# Callisto_MSO_Teknic_4BPico.net
KiCad netlist of a schematic drawn in EAGLE
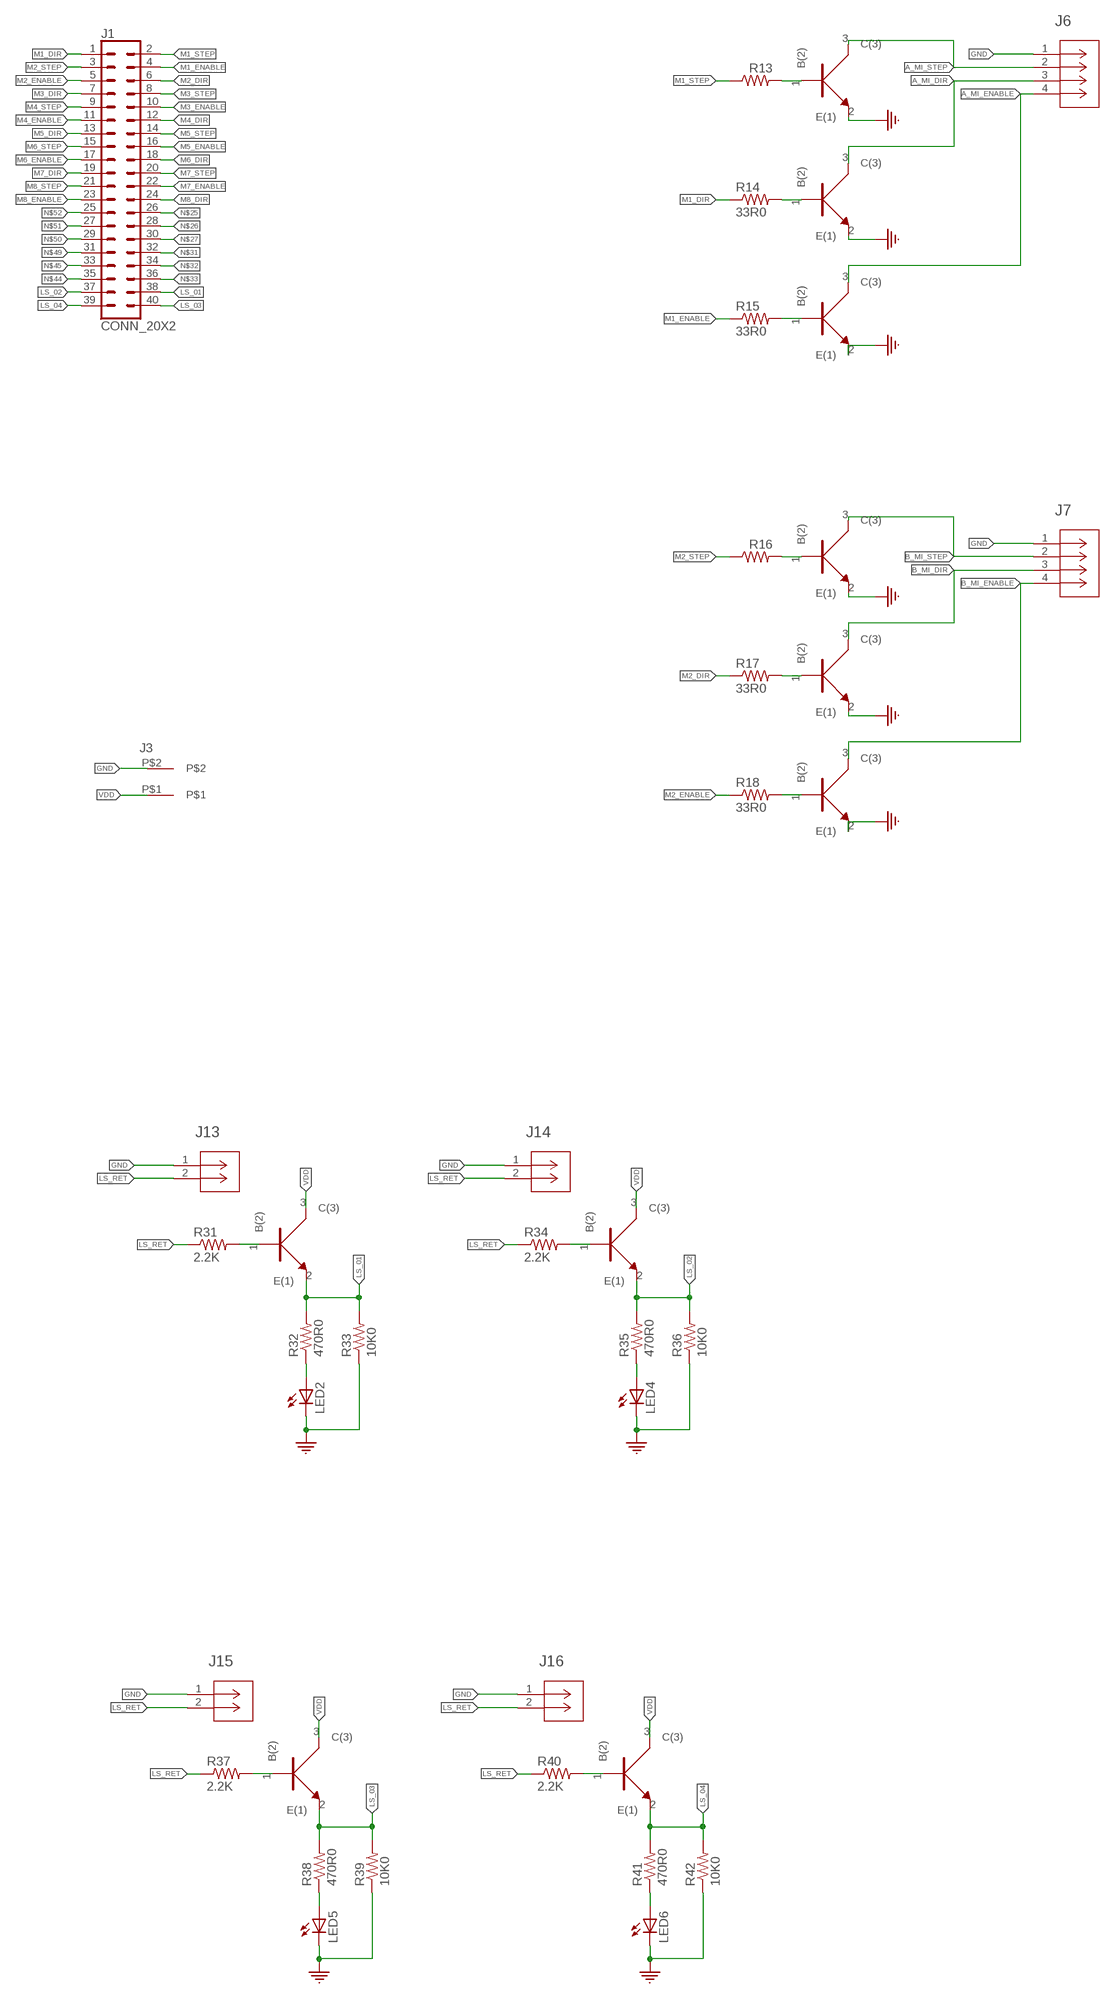
[diagram p0: schematic, sheet 1, part 1 of 2]
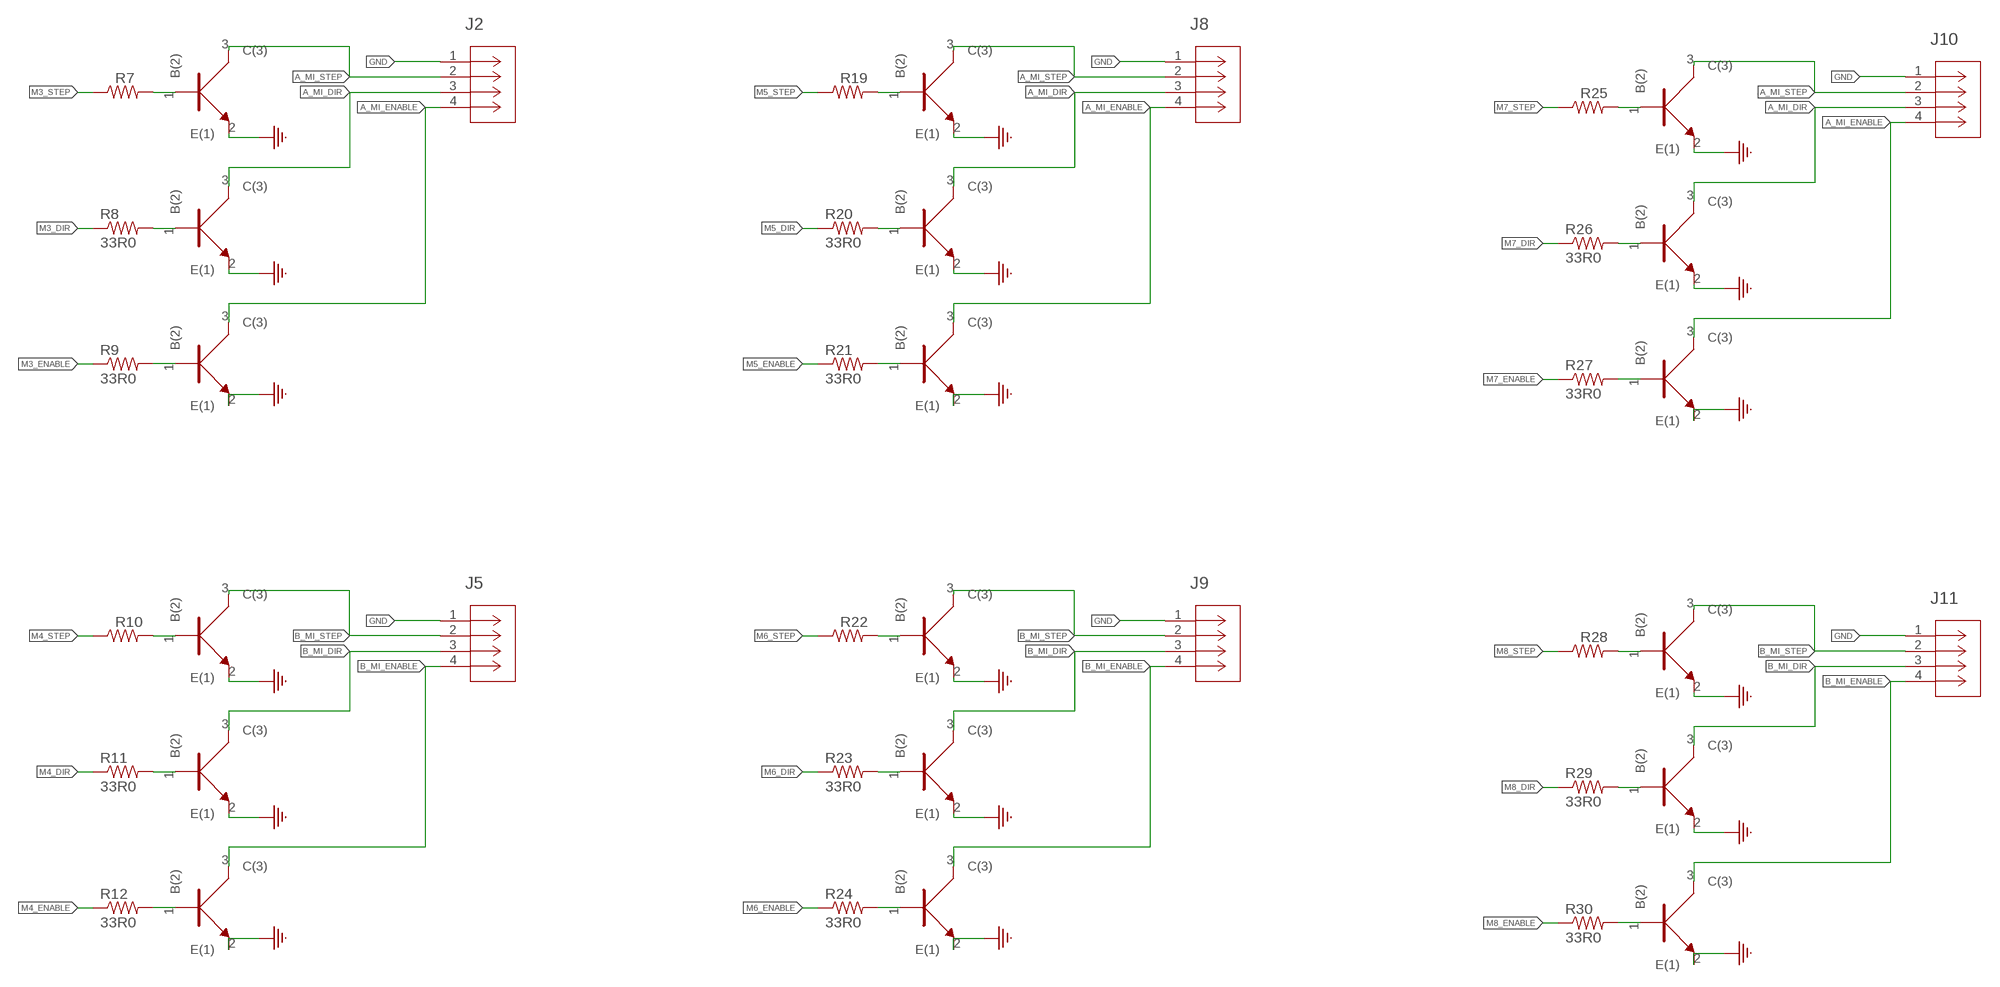
[diagram p1: schematic, sheet 1, part 2 of 2]

(export (version "E")
  (design (tool "Eeschema 10.0.6"))
  (components
    (comp (ref "J1")
      (value "CONN_20X2")
      (footprint "eagle-import:2X20")
      (libsource (lib "eagle-import") (part "CONN_20X2"))
    )
    (comp (ref "J2")
      (value "CONN_530470410_PICOBLADE_X_4")
      (footprint "eagle-import:CON_530470410_MOL")
      (fields
        (field (name "MANUFACTURER_PART_NUMBER") "530470410")
        (field (name "COPYRIGHT") "Copyright (C) 2022 Ultra Librarian. All rights reserved.")
      )
      (libsource (lib "eagle-import") (part "CONN_530470410_PICOBLADE_X_4"))
    )
    (comp (ref "J3")
      (value "2-pos")
      (footprint "eagle-import:2_3.81MM_PITCH")
      (fields (field (name "PARTNO") "691322310002"))
      (libsource (lib "eagle-import") (part "3.81MM_1_X_2_RT_ANGLE_PLUG_HEADER"))
    )
    (comp (ref "J5")
      (value "CONN_530470410_PICOBLADE_X_4")
      (footprint "eagle-import:CON_530470410_MOL")
      (fields
        (field (name "MANUFACTURER_PART_NUMBER") "530470410")
        (field (name "COPYRIGHT") "Copyright (C) 2022 Ultra Librarian. All rights reserved.")
      )
      (libsource (lib "eagle-import") (part "CONN_530470410_PICOBLADE_X_4"))
    )
    (comp (ref "J6")
      (value "CONN_530470410_PICOBLADE_X_4")
      (footprint "eagle-import:CON_530470410_MOL")
      (fields
        (field (name "MANUFACTURER_PART_NUMBER") "530470410")
        (field (name "COPYRIGHT") "Copyright (C) 2022 Ultra Librarian. All rights reserved.")
      )
      (libsource (lib "eagle-import") (part "CONN_530470410_PICOBLADE_X_4"))
    )
    (comp (ref "J7")
      (value "CONN_530470410_PICOBLADE_X_4")
      (footprint "eagle-import:CON_530470410_MOL")
      (fields
        (field (name "MANUFACTURER_PART_NUMBER") "530470410")
        (field (name "COPYRIGHT") "Copyright (C) 2022 Ultra Librarian. All rights reserved.")
      )
      (libsource (lib "eagle-import") (part "CONN_530470410_PICOBLADE_X_4"))
    )
    (comp (ref "J8")
      (value "CONN_530470410_PICOBLADE_X_4")
      (footprint "eagle-import:CON_530470410_MOL")
      (fields
        (field (name "MANUFACTURER_PART_NUMBER") "530470410")
        (field (name "COPYRIGHT") "Copyright (C) 2022 Ultra Librarian. All rights reserved.")
      )
      (libsource (lib "eagle-import") (part "CONN_530470410_PICOBLADE_X_4"))
    )
    (comp (ref "J9")
      (value "CONN_530470410_PICOBLADE_X_4")
      (footprint "eagle-import:CON_530470410_MOL")
      (fields
        (field (name "MANUFACTURER_PART_NUMBER") "530470410")
        (field (name "COPYRIGHT") "Copyright (C) 2022 Ultra Librarian. All rights reserved.")
      )
      (libsource (lib "eagle-import") (part "CONN_530470410_PICOBLADE_X_4"))
    )
    (comp (ref "J10")
      (value "CONN_530470410_PICOBLADE_X_4")
      (footprint "eagle-import:CON_530470410_MOL")
      (fields
        (field (name "MANUFACTURER_PART_NUMBER") "530470410")
        (field (name "COPYRIGHT") "Copyright (C) 2022 Ultra Librarian. All rights reserved.")
      )
      (libsource (lib "eagle-import") (part "CONN_530470410_PICOBLADE_X_4"))
    )
    (comp (ref "J11")
      (value "CONN_530470410_PICOBLADE_X_4")
      (footprint "eagle-import:CON_530470410_MOL")
      (fields
        (field (name "MANUFACTURER_PART_NUMBER") "530470410")
        (field (name "COPYRIGHT") "Copyright (C) 2022 Ultra Librarian. All rights reserved.")
      )
      (libsource (lib "eagle-import") (part "CONN_530470410_PICOBLADE_X_4"))
    )
    (comp (ref "J13")
      (value "CONN_530470210_PICOBLADE_X_2")
      (footprint "eagle-import:CON_530470210_MOL")
      (fields
        (field (name "MANUFACTURER_PART_NUMBER") "530470210")
        (field (name "COPYRIGHT") "Copyright (C) 2022 Ultra Librarian. All rights reserved.")
      )
      (libsource (lib "eagle-import") (part "CONN_530470210_PICOBLADE_X_2"))
    )
    (comp (ref "J14")
      (value "CONN_530470210_PICOBLADE_X_2")
      (footprint "eagle-import:CON_530470210_MOL")
      (fields
        (field (name "MANUFACTURER_PART_NUMBER") "530470210")
        (field (name "COPYRIGHT") "Copyright (C) 2022 Ultra Librarian. All rights reserved.")
      )
      (libsource (lib "eagle-import") (part "CONN_530470210_PICOBLADE_X_2"))
    )
    (comp (ref "J15")
      (value "CONN_530470210_PICOBLADE_X_2")
      (footprint "eagle-import:CON_530470210_MOL")
      (fields
        (field (name "MANUFACTURER_PART_NUMBER") "530470210")
        (field (name "COPYRIGHT") "Copyright (C) 2022 Ultra Librarian. All rights reserved.")
      )
      (libsource (lib "eagle-import") (part "CONN_530470210_PICOBLADE_X_2"))
    )
    (comp (ref "J16")
      (value "CONN_530470210_PICOBLADE_X_2")
      (footprint "eagle-import:CON_530470210_MOL")
      (fields
        (field (name "MANUFACTURER_PART_NUMBER") "530470210")
        (field (name "COPYRIGHT") "Copyright (C) 2022 Ultra Librarian. All rights reserved.")
      )
      (libsource (lib "eagle-import") (part "CONN_530470210_PICOBLADE_X_2"))
    )
    (comp (ref "LED2")
      (value "Green")
      (footprint "eagle-import:0805")
      (fields (field (name "PARTNO") "LG R971-KN-1"))
      (libsource (lib "eagle-import") (part "LED_0805_GREEN"))
    )
    (comp (ref "LED4")
      (value "Green")
      (footprint "eagle-import:0805")
      (fields (field (name "PARTNO") "LG R971-KN-1"))
      (libsource (lib "eagle-import") (part "LED_0805_GREEN"))
    )
    (comp (ref "LED5")
      (value "Green")
      (footprint "eagle-import:0805")
      (fields (field (name "PARTNO") "LG R971-KN-1"))
      (libsource (lib "eagle-import") (part "LED_0805_GREEN"))
    )
    (comp (ref "LED6")
      (value "Green")
      (footprint "eagle-import:0805")
      (fields (field (name "PARTNO") "LG R971-KN-1"))
      (libsource (lib "eagle-import") (part "LED_0805_GREEN"))
    )
    (comp (ref "R7")
      (value "33R0")
      (footprint "eagle-import:0402")
      (fields (field (name "PARTNO") "RMCF0402JT33R0"))
      (libsource (lib "eagle-import") (part "R_0402_33R0"))
    )
    (comp (ref "R8")
      (value "33R0")
      (footprint "eagle-import:0402")
      (fields (field (name "PARTNO") "RMCF0402JT33R0"))
      (libsource (lib "eagle-import") (part "R_0402_33R0"))
    )
    (comp (ref "R9")
      (value "33R0")
      (footprint "eagle-import:0402")
      (fields (field (name "PARTNO") "RMCF0402JT33R0"))
      (libsource (lib "eagle-import") (part "R_0402_33R0"))
    )
    (comp (ref "R10")
      (value "33R0")
      (footprint "eagle-import:0402")
      (fields (field (name "PARTNO") "RMCF0402JT33R0"))
      (libsource (lib "eagle-import") (part "R_0402_33R0"))
    )
    (comp (ref "R11")
      (value "33R0")
      (footprint "eagle-import:0402")
      (fields (field (name "PARTNO") "RMCF0402JT33R0"))
      (libsource (lib "eagle-import") (part "R_0402_33R0"))
    )
    (comp (ref "R12")
      (value "33R0")
      (footprint "eagle-import:0402")
      (fields (field (name "PARTNO") "RMCF0402JT33R0"))
      (libsource (lib "eagle-import") (part "R_0402_33R0"))
    )
    (comp (ref "R13")
      (value "33R0")
      (footprint "eagle-import:0402")
      (fields (field (name "PARTNO") "RMCF0402JT33R0"))
      (libsource (lib "eagle-import") (part "R_0402_33R0"))
    )
    (comp (ref "R14")
      (value "33R0")
      (footprint "eagle-import:0402")
      (fields (field (name "PARTNO") "RMCF0402JT33R0"))
      (libsource (lib "eagle-import") (part "R_0402_33R0"))
    )
    (comp (ref "R15")
      (value "33R0")
      (footprint "eagle-import:0402")
      (fields (field (name "PARTNO") "RMCF0402JT33R0"))
      (libsource (lib "eagle-import") (part "R_0402_33R0"))
    )
    (comp (ref "R16")
      (value "33R0")
      (footprint "eagle-import:0402")
      (fields (field (name "PARTNO") "RMCF0402JT33R0"))
      (libsource (lib "eagle-import") (part "R_0402_33R0"))
    )
    (comp (ref "R17")
      (value "33R0")
      (footprint "eagle-import:0402")
      (fields (field (name "PARTNO") "RMCF0402JT33R0"))
      (libsource (lib "eagle-import") (part "R_0402_33R0"))
    )
    (comp (ref "R18")
      (value "33R0")
      (footprint "eagle-import:0402")
      (fields (field (name "PARTNO") "RMCF0402JT33R0"))
      (libsource (lib "eagle-import") (part "R_0402_33R0"))
    )
    (comp (ref "R19")
      (value "33R0")
      (footprint "eagle-import:0402")
      (fields (field (name "PARTNO") "RMCF0402JT33R0"))
      (libsource (lib "eagle-import") (part "R_0402_33R0"))
    )
    (comp (ref "R20")
      (value "33R0")
      (footprint "eagle-import:0402")
      (fields (field (name "PARTNO") "RMCF0402JT33R0"))
      (libsource (lib "eagle-import") (part "R_0402_33R0"))
    )
    (comp (ref "R21")
      (value "33R0")
      (footprint "eagle-import:0402")
      (fields (field (name "PARTNO") "RMCF0402JT33R0"))
      (libsource (lib "eagle-import") (part "R_0402_33R0"))
    )
    (comp (ref "R22")
      (value "33R0")
      (footprint "eagle-import:0402")
      (fields (field (name "PARTNO") "RMCF0402JT33R0"))
      (libsource (lib "eagle-import") (part "R_0402_33R0"))
    )
    (comp (ref "R23")
      (value "33R0")
      (footprint "eagle-import:0402")
      (fields (field (name "PARTNO") "RMCF0402JT33R0"))
      (libsource (lib "eagle-import") (part "R_0402_33R0"))
    )
    (comp (ref "R24")
      (value "33R0")
      (footprint "eagle-import:0402")
      (fields (field (name "PARTNO") "RMCF0402JT33R0"))
      (libsource (lib "eagle-import") (part "R_0402_33R0"))
    )
    (comp (ref "R25")
      (value "33R0")
      (footprint "eagle-import:0402")
      (fields (field (name "PARTNO") "RMCF0402JT33R0"))
      (libsource (lib "eagle-import") (part "R_0402_33R0"))
    )
    (comp (ref "R26")
      (value "33R0")
      (footprint "eagle-import:0402")
      (fields (field (name "PARTNO") "RMCF0402JT33R0"))
      (libsource (lib "eagle-import") (part "R_0402_33R0"))
    )
    (comp (ref "R27")
      (value "33R0")
      (footprint "eagle-import:0402")
      (fields (field (name "PARTNO") "RMCF0402JT33R0"))
      (libsource (lib "eagle-import") (part "R_0402_33R0"))
    )
    (comp (ref "R28")
      (value "33R0")
      (footprint "eagle-import:0402")
      (fields (field (name "PARTNO") "RMCF0402JT33R0"))
      (libsource (lib "eagle-import") (part "R_0402_33R0"))
    )
    (comp (ref "R29")
      (value "33R0")
      (footprint "eagle-import:0402")
      (fields (field (name "PARTNO") "RMCF0402JT33R0"))
      (libsource (lib "eagle-import") (part "R_0402_33R0"))
    )
    (comp (ref "R30")
      (value "33R0")
      (footprint "eagle-import:0402")
      (fields (field (name "PARTNO") "RMCF0402JT33R0"))
      (libsource (lib "eagle-import") (part "R_0402_33R0"))
    )
    (comp (ref "R31")
      (value "2.2K")
      (footprint "eagle-import:0402")
      (libsource (lib "eagle-import") (part "R_0402"))
    )
    (comp (ref "R32")
      (value "470R0")
      (footprint "eagle-import:0402")
      (fields (field (name "PARTNO") "RMCF0402JT470R"))
      (libsource (lib "eagle-import") (part "R_0402_470R0"))
    )
    (comp (ref "R33")
      (value "10K0")
      (footprint "eagle-import:0402")
      (fields (field (name "PARTNO") "RMCF0402JT10K0"))
      (libsource (lib "eagle-import") (part "R_0402_10K0"))
    )
    (comp (ref "R34")
      (value "2.2K")
      (footprint "eagle-import:0402")
      (libsource (lib "eagle-import") (part "R_0402"))
    )
    (comp (ref "R35")
      (value "470R0")
      (footprint "eagle-import:0402")
      (fields (field (name "PARTNO") "RMCF0402JT470R"))
      (libsource (lib "eagle-import") (part "R_0402_470R0"))
    )
    (comp (ref "R36")
      (value "10K0")
      (footprint "eagle-import:0402")
      (fields (field (name "PARTNO") "RMCF0402JT10K0"))
      (libsource (lib "eagle-import") (part "R_0402_10K0"))
    )
    (comp (ref "R37")
      (value "2.2K")
      (footprint "eagle-import:0402")
      (libsource (lib "eagle-import") (part "R_0402"))
    )
    (comp (ref "R38")
      (value "470R0")
      (footprint "eagle-import:0402")
      (fields (field (name "PARTNO") "RMCF0402JT470R"))
      (libsource (lib "eagle-import") (part "R_0402_470R0"))
    )
    (comp (ref "R39")
      (value "10K0")
      (footprint "eagle-import:0402")
      (fields (field (name "PARTNO") "RMCF0402JT10K0"))
      (libsource (lib "eagle-import") (part "R_0402_10K0"))
    )
    (comp (ref "R40")
      (value "2.2K")
      (footprint "eagle-import:0402")
      (libsource (lib "eagle-import") (part "R_0402"))
    )
    (comp (ref "R41")
      (value "470R0")
      (footprint "eagle-import:0402")
      (fields (field (name "PARTNO") "RMCF0402JT470R"))
      (libsource (lib "eagle-import") (part "R_0402_470R0"))
    )
    (comp (ref "R42")
      (value "10K0")
      (footprint "eagle-import:0402")
      (fields (field (name "PARTNO") "RMCF0402JT10K0"))
      (libsource (lib "eagle-import") (part "R_0402_10K0"))
    )
    (comp (ref "U2")
      (value "NPN")
      (footprint "eagle-import:SOT323")
      (fields (field (name "PARTNO") "BC846BW_NPN"))
      (libsource (lib "eagle-import") (part "BC846BW"))
    )
    (comp (ref "U4")
      (value "NPN")
      (footprint "eagle-import:SOT323")
      (fields (field (name "PARTNO") "BC846BW_NPN"))
      (libsource (lib "eagle-import") (part "BC846BW"))
    )
    (comp (ref "U5")
      (value "NPN")
      (footprint "eagle-import:SOT323")
      (fields (field (name "PARTNO") "BC846BW_NPN"))
      (libsource (lib "eagle-import") (part "BC846BW"))
    )
    (comp (ref "U6")
      (value "NPN")
      (footprint "eagle-import:SOT323")
      (fields (field (name "PARTNO") "BC846BW_NPN"))
      (libsource (lib "eagle-import") (part "BC846BW"))
    )
    (comp (ref "U7")
      (value "NPN")
      (footprint "eagle-import:SOT323")
      (fields (field (name "PARTNO") "BC846BW_NPN"))
      (libsource (lib "eagle-import") (part "BC846BW"))
    )
    (comp (ref "U8")
      (value "NPN")
      (footprint "eagle-import:SOT323")
      (fields (field (name "PARTNO") "BC846BW_NPN"))
      (libsource (lib "eagle-import") (part "BC846BW"))
    )
    (comp (ref "U9")
      (value "NPN")
      (footprint "eagle-import:SOT323")
      (fields (field (name "PARTNO") "BC846BW_NPN"))
      (libsource (lib "eagle-import") (part "BC846BW"))
    )
    (comp (ref "U10")
      (value "NPN")
      (footprint "eagle-import:SOT323")
      (fields (field (name "PARTNO") "BC846BW_NPN"))
      (libsource (lib "eagle-import") (part "BC846BW"))
    )
    (comp (ref "U11")
      (value "NPN")
      (footprint "eagle-import:SOT323")
      (fields (field (name "PARTNO") "BC846BW_NPN"))
      (libsource (lib "eagle-import") (part "BC846BW"))
    )
    (comp (ref "U12")
      (value "NPN")
      (footprint "eagle-import:SOT323")
      (fields (field (name "PARTNO") "BC846BW_NPN"))
      (libsource (lib "eagle-import") (part "BC846BW"))
    )
    (comp (ref "U13")
      (value "NPN")
      (footprint "eagle-import:SOT323")
      (fields (field (name "PARTNO") "BC846BW_NPN"))
      (libsource (lib "eagle-import") (part "BC846BW"))
    )
    (comp (ref "U14")
      (value "NPN")
      (footprint "eagle-import:SOT323")
      (fields (field (name "PARTNO") "BC846BW_NPN"))
      (libsource (lib "eagle-import") (part "BC846BW"))
    )
    (comp (ref "U15")
      (value "NPN")
      (footprint "eagle-import:SOT323")
      (fields (field (name "PARTNO") "BC846BW_NPN"))
      (libsource (lib "eagle-import") (part "BC846BW"))
    )
    (comp (ref "U16")
      (value "NPN")
      (footprint "eagle-import:SOT323")
      (fields (field (name "PARTNO") "BC846BW_NPN"))
      (libsource (lib "eagle-import") (part "BC846BW"))
    )
    (comp (ref "U17")
      (value "NPN")
      (footprint "eagle-import:SOT323")
      (fields (field (name "PARTNO") "BC846BW_NPN"))
      (libsource (lib "eagle-import") (part "BC846BW"))
    )
    (comp (ref "U18")
      (value "NPN")
      (footprint "eagle-import:SOT323")
      (fields (field (name "PARTNO") "BC846BW_NPN"))
      (libsource (lib "eagle-import") (part "BC846BW"))
    )
    (comp (ref "U19")
      (value "NPN")
      (footprint "eagle-import:SOT323")
      (fields (field (name "PARTNO") "BC846BW_NPN"))
      (libsource (lib "eagle-import") (part "BC846BW"))
    )
    (comp (ref "U20")
      (value "NPN")
      (footprint "eagle-import:SOT323")
      (fields (field (name "PARTNO") "BC846BW_NPN"))
      (libsource (lib "eagle-import") (part "BC846BW"))
    )
    (comp (ref "U21")
      (value "NPN")
      (footprint "eagle-import:SOT323")
      (fields (field (name "PARTNO") "BC846BW_NPN"))
      (libsource (lib "eagle-import") (part "BC846BW"))
    )
    (comp (ref "U22")
      (value "NPN")
      (footprint "eagle-import:SOT323")
      (fields (field (name "PARTNO") "BC846BW_NPN"))
      (libsource (lib "eagle-import") (part "BC846BW"))
    )
    (comp (ref "U23")
      (value "NPN")
      (footprint "eagle-import:SOT323")
      (fields (field (name "PARTNO") "BC846BW_NPN"))
      (libsource (lib "eagle-import") (part "BC846BW"))
    )
    (comp (ref "U24")
      (value "NPN")
      (footprint "eagle-import:SOT323")
      (fields (field (name "PARTNO") "BC846BW_NPN"))
      (libsource (lib "eagle-import") (part "BC846BW"))
    )
    (comp (ref "U25")
      (value "NPN")
      (footprint "eagle-import:SOT323")
      (fields (field (name "PARTNO") "BC846BW_NPN"))
      (libsource (lib "eagle-import") (part "BC846BW"))
    )
    (comp (ref "U26")
      (value "NPN")
      (footprint "eagle-import:SOT323")
      (fields (field (name "PARTNO") "BC846BW_NPN"))
      (libsource (lib "eagle-import") (part "BC846BW"))
    )
    (comp (ref "U27")
      (value "NPN")
      (footprint "eagle-import:SOT323")
      (fields (field (name "PARTNO") "BC846BW_NPN"))
      (libsource (lib "eagle-import") (part "BC846BW"))
    )
    (comp (ref "U28")
      (value "NPN")
      (footprint "eagle-import:SOT323")
      (fields (field (name "PARTNO") "BC846BW_NPN"))
      (libsource (lib "eagle-import") (part "BC846BW"))
    )
    (comp (ref "U29")
      (value "NPN")
      (footprint "eagle-import:SOT323")
      (fields (field (name "PARTNO") "BC846BW_NPN"))
      (libsource (lib "eagle-import") (part "BC846BW"))
    )
    (comp (ref "U30")
      (value "NPN")
      (footprint "eagle-import:SOT323")
      (fields (field (name "PARTNO") "BC846BW_NPN"))
      (libsource (lib "eagle-import") (part "BC846BW"))
    )
  )
  (nets
    (net (code "1") (name "A_MI_DIR") (class "Default")
      (node (ref "J10") (pin "3") (pinfunction "3_3") (pintype "passive"))
      (node (ref "J2") (pin "3") (pinfunction "3_3") (pintype "passive"))
      (node (ref "J6") (pin "3") (pinfunction "3_3") (pintype "passive"))
      (node (ref "J8") (pin "3") (pinfunction "3_3") (pintype "passive"))
      (node (ref "U14") (pin "3") (pinfunction "C(3)_3") (pintype "input"))
      (node (ref "U20") (pin "3") (pinfunction "C(3)_3") (pintype "input"))
      (node (ref "U26") (pin "3") (pinfunction "C(3)_3") (pintype "input"))
      (node (ref "U8") (pin "3") (pinfunction "C(3)_3") (pintype "input"))
    )
    (net (code "2") (name "A_MI_ENABLE") (class "Default")
      (node (ref "J10") (pin "4") (pinfunction "4_4") (pintype "passive"))
      (node (ref "J2") (pin "4") (pinfunction "4_4") (pintype "passive"))
      (node (ref "J6") (pin "4") (pinfunction "4_4") (pintype "passive"))
      (node (ref "J8") (pin "4") (pinfunction "4_4") (pintype "passive"))
      (node (ref "U15") (pin "3") (pinfunction "C(3)_3") (pintype "input"))
      (node (ref "U21") (pin "3") (pinfunction "C(3)_3") (pintype "input"))
      (node (ref "U27") (pin "3") (pinfunction "C(3)_3") (pintype "input"))
      (node (ref "U9") (pin "3") (pinfunction "C(3)_3") (pintype "input"))
    )
    (net (code "3") (name "A_MI_STEP") (class "Default")
      (node (ref "J10") (pin "2") (pinfunction "2_2") (pintype "passive"))
      (node (ref "J2") (pin "2") (pinfunction "2_2") (pintype "passive"))
      (node (ref "J6") (pin "2") (pinfunction "2_2") (pintype "passive"))
      (node (ref "J8") (pin "2") (pinfunction "2_2") (pintype "passive"))
      (node (ref "U13") (pin "3") (pinfunction "C(3)_3") (pintype "input"))
      (node (ref "U19") (pin "3") (pinfunction "C(3)_3") (pintype "input"))
      (node (ref "U25") (pin "3") (pinfunction "C(3)_3") (pintype "input"))
      (node (ref "U7") (pin "3") (pinfunction "C(3)_3") (pintype "input"))
    )
    (net (code "4") (name "B_MI_DIR") (class "Default")
      (node (ref "J11") (pin "3") (pinfunction "3_3") (pintype "passive"))
      (node (ref "J5") (pin "3") (pinfunction "3_3") (pintype "passive"))
      (node (ref "J7") (pin "3") (pinfunction "3_3") (pintype "passive"))
      (node (ref "J9") (pin "3") (pinfunction "3_3") (pintype "passive"))
      (node (ref "U11") (pin "3") (pinfunction "C(3)_3") (pintype "input"))
      (node (ref "U17") (pin "3") (pinfunction "C(3)_3") (pintype "input"))
      (node (ref "U23") (pin "3") (pinfunction "C(3)_3") (pintype "input"))
      (node (ref "U29") (pin "3") (pinfunction "C(3)_3") (pintype "input"))
    )
    (net (code "5") (name "B_MI_ENABLE") (class "Default")
      (node (ref "J11") (pin "4") (pinfunction "4_4") (pintype "passive"))
      (node (ref "J5") (pin "4") (pinfunction "4_4") (pintype "passive"))
      (node (ref "J7") (pin "4") (pinfunction "4_4") (pintype "passive"))
      (node (ref "J9") (pin "4") (pinfunction "4_4") (pintype "passive"))
      (node (ref "U12") (pin "3") (pinfunction "C(3)_3") (pintype "input"))
      (node (ref "U18") (pin "3") (pinfunction "C(3)_3") (pintype "input"))
      (node (ref "U24") (pin "3") (pinfunction "C(3)_3") (pintype "input"))
      (node (ref "U30") (pin "3") (pinfunction "C(3)_3") (pintype "input"))
    )
    (net (code "6") (name "B_MI_STEP") (class "Default")
      (node (ref "J11") (pin "2") (pinfunction "2_2") (pintype "passive"))
      (node (ref "J5") (pin "2") (pinfunction "2_2") (pintype "passive"))
      (node (ref "J7") (pin "2") (pinfunction "2_2") (pintype "passive"))
      (node (ref "J9") (pin "2") (pinfunction "2_2") (pintype "passive"))
      (node (ref "U10") (pin "3") (pinfunction "C(3)_3") (pintype "input"))
      (node (ref "U16") (pin "3") (pinfunction "C(3)_3") (pintype "input"))
      (node (ref "U22") (pin "3") (pinfunction "C(3)_3") (pintype "input"))
      (node (ref "U28") (pin "3") (pinfunction "C(3)_3") (pintype "input"))
    )
    (net (code "7") (name "GND") (class "Default")
      (node (ref "J10") (pin "1") (pinfunction "1_1") (pintype "passive"))
      (node (ref "J11") (pin "1") (pinfunction "1_1") (pintype "passive"))
      (node (ref "J13") (pin "1") (pinfunction "1_1") (pintype "passive"))
      (node (ref "J14") (pin "1") (pinfunction "1_1") (pintype "passive"))
      (node (ref "J15") (pin "1") (pinfunction "1_1") (pintype "passive"))
      (node (ref "J16") (pin "1") (pinfunction "1_1") (pintype "passive"))
      (node (ref "J2") (pin "1") (pinfunction "1_1") (pintype "passive"))
      (node (ref "J3") (pin "P$2") (pinfunction "P$2_P$2") (pintype "bidirectional"))
      (node (ref "J5") (pin "1") (pinfunction "1_1") (pintype "passive"))
      (node (ref "J6") (pin "1") (pinfunction "1_1") (pintype "passive"))
      (node (ref "J7") (pin "1") (pinfunction "1_1") (pintype "passive"))
      (node (ref "J8") (pin "1") (pinfunction "1_1") (pintype "passive"))
      (node (ref "J9") (pin "1") (pinfunction "1_1") (pintype "passive"))
      (node (ref "LED2") (pin "2") (pinfunction "C_2") (pintype "passive"))
      (node (ref "LED4") (pin "2") (pinfunction "C_2") (pintype "passive"))
      (node (ref "LED5") (pin "2") (pinfunction "C_2") (pintype "passive"))
      (node (ref "LED6") (pin "2") (pinfunction "C_2") (pintype "passive"))
      (node (ref "R33") (pin "P$1") (pinfunction "1_P$1") (pintype "passive"))
      (node (ref "R36") (pin "P$1") (pinfunction "1_P$1") (pintype "passive"))
      (node (ref "R39") (pin "P$1") (pinfunction "1_P$1") (pintype "passive"))
      (node (ref "R42") (pin "P$1") (pinfunction "1_P$1") (pintype "passive"))
      (node (ref "U10") (pin "2") (pinfunction "E(1)_2") (pintype "output"))
      (node (ref "U11") (pin "2") (pinfunction "E(1)_2") (pintype "output"))
      (node (ref "U12") (pin "2") (pinfunction "E(1)_2") (pintype "output"))
      (node (ref "U13") (pin "2") (pinfunction "E(1)_2") (pintype "output"))
      (node (ref "U14") (pin "2") (pinfunction "E(1)_2") (pintype "output"))
      (node (ref "U15") (pin "2") (pinfunction "E(1)_2") (pintype "output"))
      (node (ref "U16") (pin "2") (pinfunction "E(1)_2") (pintype "output"))
      (node (ref "U17") (pin "2") (pinfunction "E(1)_2") (pintype "output"))
      (node (ref "U18") (pin "2") (pinfunction "E(1)_2") (pintype "output"))
      (node (ref "U19") (pin "2") (pinfunction "E(1)_2") (pintype "output"))
      (node (ref "U20") (pin "2") (pinfunction "E(1)_2") (pintype "output"))
      (node (ref "U21") (pin "2") (pinfunction "E(1)_2") (pintype "output"))
      (node (ref "U22") (pin "2") (pinfunction "E(1)_2") (pintype "output"))
      (node (ref "U23") (pin "2") (pinfunction "E(1)_2") (pintype "output"))
      (node (ref "U24") (pin "2") (pinfunction "E(1)_2") (pintype "output"))
      (node (ref "U25") (pin "2") (pinfunction "E(1)_2") (pintype "output"))
      (node (ref "U26") (pin "2") (pinfunction "E(1)_2") (pintype "output"))
      (node (ref "U27") (pin "2") (pinfunction "E(1)_2") (pintype "output"))
      (node (ref "U28") (pin "2") (pinfunction "E(1)_2") (pintype "output"))
      (node (ref "U29") (pin "2") (pinfunction "E(1)_2") (pintype "output"))
      (node (ref "U30") (pin "2") (pinfunction "E(1)_2") (pintype "output"))
      (node (ref "U7") (pin "2") (pinfunction "E(1)_2") (pintype "output"))
      (node (ref "U8") (pin "2") (pinfunction "E(1)_2") (pintype "output"))
      (node (ref "U9") (pin "2") (pinfunction "E(1)_2") (pintype "output"))
    )
    (net (code "8") (name "LS_01") (class "Default")
      (node (ref "J1") (pin "38") (pinfunction "38_38") (pintype "passive"))
      (node (ref "R32") (pin "P$2") (pinfunction "2_P$2") (pintype "passive"))
      (node (ref "R33") (pin "P$2") (pinfunction "2_P$2") (pintype "passive"))
      (node (ref "U2") (pin "2") (pinfunction "E(1)_2") (pintype "output"))
    )
    (net (code "9") (name "LS_02") (class "Default")
      (node (ref "J1") (pin "37") (pinfunction "37_37") (pintype "passive"))
      (node (ref "R35") (pin "P$2") (pinfunction "2_P$2") (pintype "passive"))
      (node (ref "R36") (pin "P$2") (pinfunction "2_P$2") (pintype "passive"))
      (node (ref "U4") (pin "2") (pinfunction "E(1)_2") (pintype "output"))
    )
    (net (code "10") (name "LS_03") (class "Default")
      (node (ref "J1") (pin "40") (pinfunction "40_40") (pintype "passive"))
      (node (ref "R38") (pin "P$2") (pinfunction "2_P$2") (pintype "passive"))
      (node (ref "R39") (pin "P$2") (pinfunction "2_P$2") (pintype "passive"))
      (node (ref "U5") (pin "2") (pinfunction "E(1)_2") (pintype "output"))
    )
    (net (code "11") (name "LS_04") (class "Default")
      (node (ref "J1") (pin "39") (pinfunction "39_39") (pintype "passive"))
      (node (ref "R41") (pin "P$2") (pinfunction "2_P$2") (pintype "passive"))
      (node (ref "R42") (pin "P$2") (pinfunction "2_P$2") (pintype "passive"))
      (node (ref "U6") (pin "2") (pinfunction "E(1)_2") (pintype "output"))
    )
    (net (code "12") (name "LS_RET") (class "Default")
      (node (ref "J13") (pin "2") (pinfunction "2_2") (pintype "passive"))
      (node (ref "J14") (pin "2") (pinfunction "2_2") (pintype "passive"))
      (node (ref "J15") (pin "2") (pinfunction "2_2") (pintype "passive"))
      (node (ref "J16") (pin "2") (pinfunction "2_2") (pintype "passive"))
      (node (ref "R31") (pin "P$1") (pinfunction "1_P$1") (pintype "passive"))
      (node (ref "R34") (pin "P$1") (pinfunction "1_P$1") (pintype "passive"))
      (node (ref "R37") (pin "P$1") (pinfunction "1_P$1") (pintype "passive"))
      (node (ref "R40") (pin "P$1") (pinfunction "1_P$1") (pintype "passive"))
    )
    (net (code "13") (name "M1_DIR") (class "Default")
      (node (ref "J1") (pin "1") (pinfunction "1_1") (pintype "passive"))
      (node (ref "R14") (pin "P$1") (pinfunction "1_P$1") (pintype "passive"))
    )
    (net (code "14") (name "M1_ENABLE") (class "Default")
      (node (ref "J1") (pin "4") (pinfunction "4_4") (pintype "passive"))
      (node (ref "R15") (pin "P$1") (pinfunction "1_P$1") (pintype "passive"))
    )
    (net (code "15") (name "M1_STEP") (class "Default")
      (node (ref "J1") (pin "2") (pinfunction "2_2") (pintype "passive"))
      (node (ref "R13") (pin "P$1") (pinfunction "1_P$1") (pintype "passive"))
    )
    (net (code "16") (name "M2_DIR") (class "Default")
      (node (ref "J1") (pin "6") (pinfunction "6_6") (pintype "passive"))
      (node (ref "R17") (pin "P$1") (pinfunction "1_P$1") (pintype "passive"))
    )
    (net (code "17") (name "M2_ENABLE") (class "Default")
      (node (ref "J1") (pin "5") (pinfunction "5_5") (pintype "passive"))
      (node (ref "R18") (pin "P$1") (pinfunction "1_P$1") (pintype "passive"))
    )
    (net (code "18") (name "M2_STEP") (class "Default")
      (node (ref "J1") (pin "3") (pinfunction "3_3") (pintype "passive"))
      (node (ref "R16") (pin "P$1") (pinfunction "1_P$1") (pintype "passive"))
    )
    (net (code "19") (name "M3_DIR") (class "Default")
      (node (ref "J1") (pin "7") (pinfunction "7_7") (pintype "passive"))
      (node (ref "R8") (pin "P$1") (pinfunction "1_P$1") (pintype "passive"))
    )
    (net (code "20") (name "M3_ENABLE") (class "Default")
      (node (ref "J1") (pin "10") (pinfunction "10_10") (pintype "passive"))
      (node (ref "R9") (pin "P$1") (pinfunction "1_P$1") (pintype "passive"))
    )
    (net (code "21") (name "M3_STEP") (class "Default")
      (node (ref "J1") (pin "8") (pinfunction "8_8") (pintype "passive"))
      (node (ref "R7") (pin "P$1") (pinfunction "1_P$1") (pintype "passive"))
    )
    (net (code "22") (name "M4_DIR") (class "Default")
      (node (ref "J1") (pin "12") (pinfunction "12_12") (pintype "passive"))
      (node (ref "R11") (pin "P$1") (pinfunction "1_P$1") (pintype "passive"))
    )
    (net (code "23") (name "M4_ENABLE") (class "Default")
      (node (ref "J1") (pin "11") (pinfunction "11_11") (pintype "passive"))
      (node (ref "R12") (pin "P$1") (pinfunction "1_P$1") (pintype "passive"))
    )
    (net (code "24") (name "M4_STEP") (class "Default")
      (node (ref "J1") (pin "9") (pinfunction "9_9") (pintype "passive"))
      (node (ref "R10") (pin "P$1") (pinfunction "1_P$1") (pintype "passive"))
    )
    (net (code "25") (name "M5_DIR") (class "Default")
      (node (ref "J1") (pin "13") (pinfunction "13_13") (pintype "passive"))
      (node (ref "R20") (pin "P$1") (pinfunction "1_P$1") (pintype "passive"))
    )
    (net (code "26") (name "M5_ENABLE") (class "Default")
      (node (ref "J1") (pin "16") (pinfunction "16_16") (pintype "passive"))
      (node (ref "R21") (pin "P$1") (pinfunction "1_P$1") (pintype "passive"))
    )
    (net (code "27") (name "M5_STEP") (class "Default")
      (node (ref "J1") (pin "14") (pinfunction "14_14") (pintype "passive"))
      (node (ref "R19") (pin "P$1") (pinfunction "1_P$1") (pintype "passive"))
    )
    (net (code "28") (name "M6_DIR") (class "Default")
      (node (ref "J1") (pin "18") (pinfunction "18_18") (pintype "passive"))
      (node (ref "R23") (pin "P$1") (pinfunction "1_P$1") (pintype "passive"))
    )
    (net (code "29") (name "M6_ENABLE") (class "Default")
      (node (ref "J1") (pin "17") (pinfunction "17_17") (pintype "passive"))
      (node (ref "R24") (pin "P$1") (pinfunction "1_P$1") (pintype "passive"))
    )
    (net (code "30") (name "M6_STEP") (class "Default")
      (node (ref "J1") (pin "15") (pinfunction "15_15") (pintype "passive"))
      (node (ref "R22") (pin "P$1") (pinfunction "1_P$1") (pintype "passive"))
    )
    (net (code "31") (name "M7_DIR") (class "Default")
      (node (ref "J1") (pin "19") (pinfunction "19_19") (pintype "passive"))
      (node (ref "R26") (pin "P$1") (pinfunction "1_P$1") (pintype "passive"))
    )
    (net (code "32") (name "M7_ENABLE") (class "Default")
      (node (ref "J1") (pin "22") (pinfunction "22_22") (pintype "passive"))
      (node (ref "R27") (pin "P$1") (pinfunction "1_P$1") (pintype "passive"))
    )
    (net (code "33") (name "M7_STEP") (class "Default")
      (node (ref "J1") (pin "20") (pinfunction "20_20") (pintype "passive"))
      (node (ref "R25") (pin "P$1") (pinfunction "1_P$1") (pintype "passive"))
    )
    (net (code "34") (name "M8_DIR") (class "Default")
      (node (ref "J1") (pin "24") (pinfunction "24_24") (pintype "passive"))
      (node (ref "R29") (pin "P$1") (pinfunction "1_P$1") (pintype "passive"))
    )
    (net (code "35") (name "M8_ENABLE") (class "Default")
      (node (ref "J1") (pin "23") (pinfunction "23_23") (pintype "passive"))
      (node (ref "R30") (pin "P$1") (pinfunction "1_P$1") (pintype "passive"))
    )
    (net (code "36") (name "M8_STEP") (class "Default")
      (node (ref "J1") (pin "21") (pinfunction "21_21") (pintype "passive"))
      (node (ref "R28") (pin "P$1") (pinfunction "1_P$1") (pintype "passive"))
    )
    (net (code "37") (name "N$25") (class "Default")
      (node (ref "J1") (pin "26") (pinfunction "26_26") (pintype "passive"))
    )
    (net (code "38") (name "N$26") (class "Default")
      (node (ref "J1") (pin "28") (pinfunction "28_28") (pintype "passive"))
    )
    (net (code "39") (name "N$27") (class "Default")
      (node (ref "J1") (pin "30") (pinfunction "30_30") (pintype "passive"))
    )
    (net (code "40") (name "N$31") (class "Default")
      (node (ref "J1") (pin "32") (pinfunction "32_32") (pintype "passive"))
    )
    (net (code "41") (name "N$32") (class "Default")
      (node (ref "J1") (pin "34") (pinfunction "34_34") (pintype "passive"))
    )
    (net (code "42") (name "N$33") (class "Default")
      (node (ref "J1") (pin "36") (pinfunction "36_36") (pintype "passive"))
    )
    (net (code "43") (name "N$44") (class "Default")
      (node (ref "J1") (pin "35") (pinfunction "35_35") (pintype "passive"))
    )
    (net (code "44") (name "N$45") (class "Default")
      (node (ref "J1") (pin "33") (pinfunction "33_33") (pintype "passive"))
    )
    (net (code "45") (name "N$49") (class "Default")
      (node (ref "J1") (pin "31") (pinfunction "31_31") (pintype "passive"))
    )
    (net (code "46") (name "N$50") (class "Default")
      (node (ref "J1") (pin "29") (pinfunction "29_29") (pintype "passive"))
    )
    (net (code "47") (name "N$51") (class "Default")
      (node (ref "J1") (pin "27") (pinfunction "27_27") (pintype "passive"))
    )
    (net (code "48") (name "N$52") (class "Default")
      (node (ref "J1") (pin "25") (pinfunction "25_25") (pintype "passive"))
    )
    (net (code "49") (name "Net-(LED2-A)") (class "Default")
      (node (ref "LED2") (pin "1") (pinfunction "A_1") (pintype "passive"))
      (node (ref "R32") (pin "P$1") (pinfunction "1_P$1") (pintype "passive"))
    )
    (net (code "50") (name "Net-(LED4-A)") (class "Default")
      (node (ref "LED4") (pin "1") (pinfunction "A_1") (pintype "passive"))
      (node (ref "R35") (pin "P$1") (pinfunction "1_P$1") (pintype "passive"))
    )
    (net (code "51") (name "Net-(LED5-A)") (class "Default")
      (node (ref "LED5") (pin "1") (pinfunction "A_1") (pintype "passive"))
      (node (ref "R38") (pin "P$1") (pinfunction "1_P$1") (pintype "passive"))
    )
    (net (code "52") (name "Net-(LED6-A)") (class "Default")
      (node (ref "LED6") (pin "1") (pinfunction "A_1") (pintype "passive"))
      (node (ref "R41") (pin "P$1") (pinfunction "1_P$1") (pintype "passive"))
    )
    (net (code "53") (name "Net-(R7-2)") (class "Default")
      (node (ref "R7") (pin "P$2") (pinfunction "2_P$2") (pintype "passive"))
      (node (ref "U7") (pin "1") (pinfunction "B(2)_1") (pintype "input"))
    )
    (net (code "54") (name "Net-(R8-2)") (class "Default")
      (node (ref "R8") (pin "P$2") (pinfunction "2_P$2") (pintype "passive"))
      (node (ref "U8") (pin "1") (pinfunction "B(2)_1") (pintype "input"))
    )
    (net (code "55") (name "Net-(R9-2)") (class "Default")
      (node (ref "R9") (pin "P$2") (pinfunction "2_P$2") (pintype "passive"))
      (node (ref "U9") (pin "1") (pinfunction "B(2)_1") (pintype "input"))
    )
    (net (code "56") (name "Net-(R10-2)") (class "Default")
      (node (ref "R10") (pin "P$2") (pinfunction "2_P$2") (pintype "passive"))
      (node (ref "U10") (pin "1") (pinfunction "B(2)_1") (pintype "input"))
    )
    (net (code "57") (name "Net-(R11-2)") (class "Default")
      (node (ref "R11") (pin "P$2") (pinfunction "2_P$2") (pintype "passive"))
      (node (ref "U11") (pin "1") (pinfunction "B(2)_1") (pintype "input"))
    )
    (net (code "58") (name "Net-(R12-2)") (class "Default")
      (node (ref "R12") (pin "P$2") (pinfunction "2_P$2") (pintype "passive"))
      (node (ref "U12") (pin "1") (pinfunction "B(2)_1") (pintype "input"))
    )
    (net (code "59") (name "Net-(R13-2)") (class "Default")
      (node (ref "R13") (pin "P$2") (pinfunction "2_P$2") (pintype "passive"))
      (node (ref "U13") (pin "1") (pinfunction "B(2)_1") (pintype "input"))
    )
    (net (code "60") (name "Net-(R14-2)") (class "Default")
      (node (ref "R14") (pin "P$2") (pinfunction "2_P$2") (pintype "passive"))
      (node (ref "U14") (pin "1") (pinfunction "B(2)_1") (pintype "input"))
    )
    (net (code "61") (name "Net-(R15-2)") (class "Default")
      (node (ref "R15") (pin "P$2") (pinfunction "2_P$2") (pintype "passive"))
      (node (ref "U15") (pin "1") (pinfunction "B(2)_1") (pintype "input"))
    )
    (net (code "62") (name "Net-(R16-2)") (class "Default")
      (node (ref "R16") (pin "P$2") (pinfunction "2_P$2") (pintype "passive"))
      (node (ref "U16") (pin "1") (pinfunction "B(2)_1") (pintype "input"))
    )
    (net (code "63") (name "Net-(R17-2)") (class "Default")
      (node (ref "R17") (pin "P$2") (pinfunction "2_P$2") (pintype "passive"))
      (node (ref "U17") (pin "1") (pinfunction "B(2)_1") (pintype "input"))
    )
    (net (code "64") (name "Net-(R18-2)") (class "Default")
      (node (ref "R18") (pin "P$2") (pinfunction "2_P$2") (pintype "passive"))
      (node (ref "U18") (pin "1") (pinfunction "B(2)_1") (pintype "input"))
    )
    (net (code "65") (name "Net-(R19-2)") (class "Default")
      (node (ref "R19") (pin "P$2") (pinfunction "2_P$2") (pintype "passive"))
      (node (ref "U19") (pin "1") (pinfunction "B(2)_1") (pintype "input"))
    )
    (net (code "66") (name "Net-(R20-2)") (class "Default")
      (node (ref "R20") (pin "P$2") (pinfunction "2_P$2") (pintype "passive"))
      (node (ref "U20") (pin "1") (pinfunction "B(2)_1") (pintype "input"))
    )
    (net (code "67") (name "Net-(R21-2)") (class "Default")
      (node (ref "R21") (pin "P$2") (pinfunction "2_P$2") (pintype "passive"))
      (node (ref "U21") (pin "1") (pinfunction "B(2)_1") (pintype "input"))
    )
    (net (code "68") (name "Net-(R22-2)") (class "Default")
      (node (ref "R22") (pin "P$2") (pinfunction "2_P$2") (pintype "passive"))
      (node (ref "U22") (pin "1") (pinfunction "B(2)_1") (pintype "input"))
    )
    (net (code "69") (name "Net-(R23-2)") (class "Default")
      (node (ref "R23") (pin "P$2") (pinfunction "2_P$2") (pintype "passive"))
      (node (ref "U23") (pin "1") (pinfunction "B(2)_1") (pintype "input"))
    )
    (net (code "70") (name "Net-(R24-2)") (class "Default")
      (node (ref "R24") (pin "P$2") (pinfunction "2_P$2") (pintype "passive"))
      (node (ref "U24") (pin "1") (pinfunction "B(2)_1") (pintype "input"))
    )
    (net (code "71") (name "Net-(R25-2)") (class "Default")
      (node (ref "R25") (pin "P$2") (pinfunction "2_P$2") (pintype "passive"))
      (node (ref "U25") (pin "1") (pinfunction "B(2)_1") (pintype "input"))
    )
    (net (code "72") (name "Net-(R26-2)") (class "Default")
      (node (ref "R26") (pin "P$2") (pinfunction "2_P$2") (pintype "passive"))
      (node (ref "U26") (pin "1") (pinfunction "B(2)_1") (pintype "input"))
    )
    (net (code "73") (name "Net-(R27-2)") (class "Default")
      (node (ref "R27") (pin "P$2") (pinfunction "2_P$2") (pintype "passive"))
      (node (ref "U27") (pin "1") (pinfunction "B(2)_1") (pintype "input"))
    )
    (net (code "74") (name "Net-(R28-2)") (class "Default")
      (node (ref "R28") (pin "P$2") (pinfunction "2_P$2") (pintype "passive"))
      (node (ref "U28") (pin "1") (pinfunction "B(2)_1") (pintype "input"))
    )
    (net (code "75") (name "Net-(R29-2)") (class "Default")
      (node (ref "R29") (pin "P$2") (pinfunction "2_P$2") (pintype "passive"))
      (node (ref "U29") (pin "1") (pinfunction "B(2)_1") (pintype "input"))
    )
    (net (code "76") (name "Net-(R30-2)") (class "Default")
      (node (ref "R30") (pin "P$2") (pinfunction "2_P$2") (pintype "passive"))
      (node (ref "U30") (pin "1") (pinfunction "B(2)_1") (pintype "input"))
    )
    (net (code "77") (name "Net-(R31-2)") (class "Default")
      (node (ref "R31") (pin "P$2") (pinfunction "2_P$2") (pintype "passive"))
      (node (ref "U2") (pin "1") (pinfunction "B(2)_1") (pintype "input"))
    )
    (net (code "78") (name "Net-(R34-2)") (class "Default")
      (node (ref "R34") (pin "P$2") (pinfunction "2_P$2") (pintype "passive"))
      (node (ref "U4") (pin "1") (pinfunction "B(2)_1") (pintype "input"))
    )
    (net (code "79") (name "Net-(R37-2)") (class "Default")
      (node (ref "R37") (pin "P$2") (pinfunction "2_P$2") (pintype "passive"))
      (node (ref "U5") (pin "1") (pinfunction "B(2)_1") (pintype "input"))
    )
    (net (code "80") (name "Net-(R40-2)") (class "Default")
      (node (ref "R40") (pin "P$2") (pinfunction "2_P$2") (pintype "passive"))
      (node (ref "U6") (pin "1") (pinfunction "B(2)_1") (pintype "input"))
    )
    (net (code "81") (name "VDD") (class "Default")
      (node (ref "J3") (pin "P$1") (pinfunction "P$1_P$1") (pintype "bidirectional"))
      (node (ref "U2") (pin "3") (pinfunction "C(3)_3") (pintype "input"))
      (node (ref "U4") (pin "3") (pinfunction "C(3)_3") (pintype "input"))
      (node (ref "U5") (pin "3") (pinfunction "C(3)_3") (pintype "input"))
      (node (ref "U6") (pin "3") (pinfunction "C(3)_3") (pintype "input"))
    )
  )
)
